# MCU.net
KiCad netlist of a schematic drawn in Altium Designer
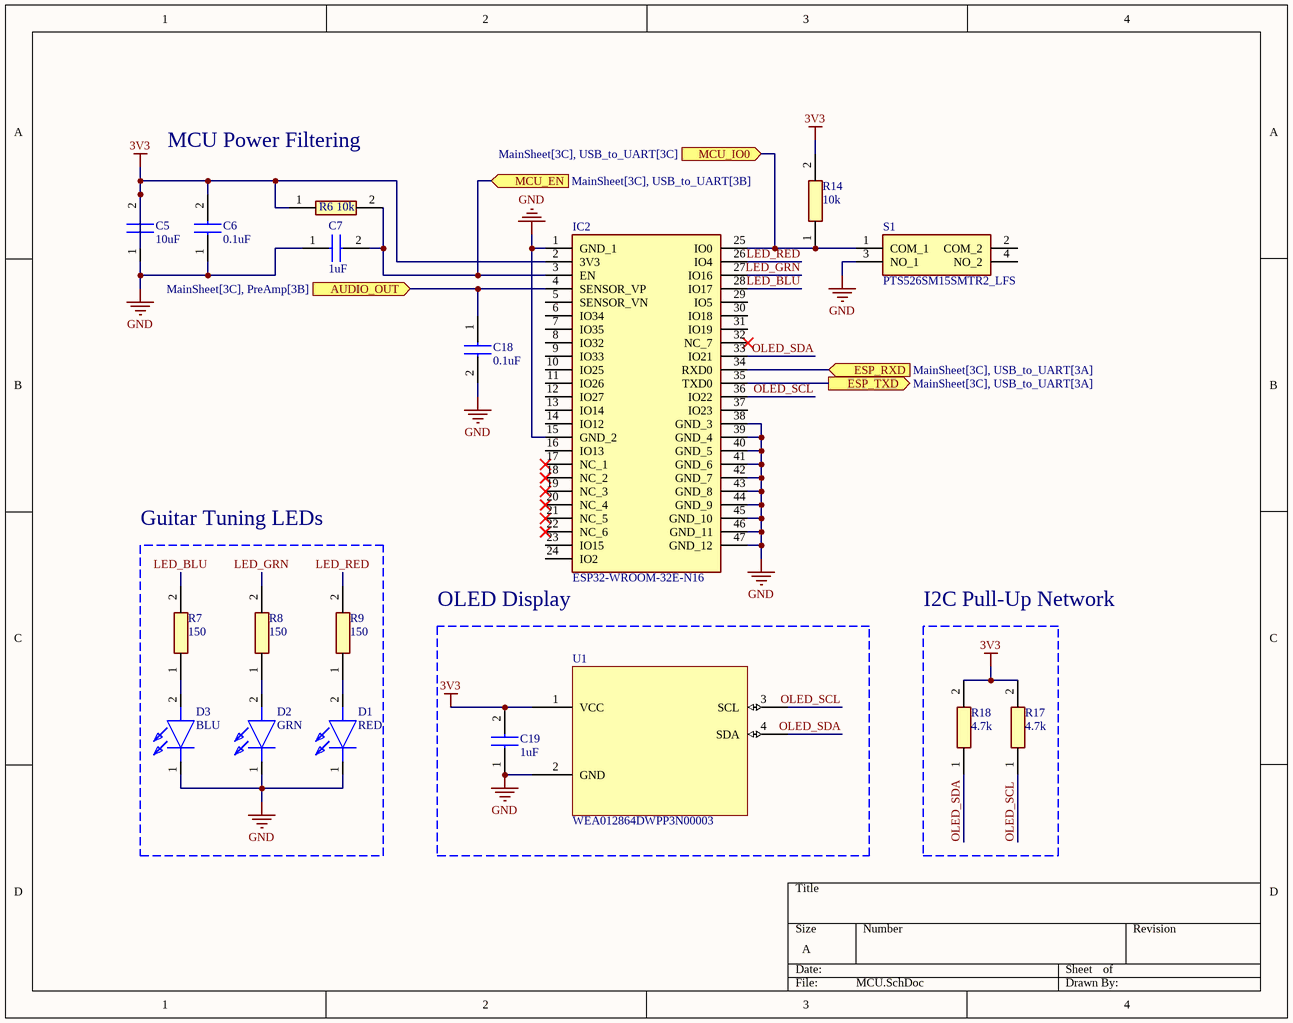
[diagram p0: MCU.SchDoc]

(export (version "E")
  (design (tool "Eeschema 10.0.6"))
  (components
    (comp (ref "C5")
      (value "10uF")
      (footprint "SamacSys:CAPC2012X140N")
      (description "Capacitor")
      (fields (field (name "MANUFACTURER_PART_NUMBER") "C0805C106K8PACTU-2.5"))
      (libsource (lib "Schlib1") (part "10uF Capacitor 0805"))
    )
    (comp (ref "C6")
      (value "0.1uF")
      (footprint "SamacSys:CAPC2012X88N")
      (description "Capacitor")
      (fields (field (name "MANUFACTURER_PART_NUMBER") "C0805C104K5RAC-TU"))
      (libsource (lib "Schlib1") (part "0.1uF Capacitor 0805"))
    )
    (comp (ref "C7")
      (value "1uF")
      (footprint "SamacSys:CAPC2012X145N")
      (description "Capacitor")
      (fields
        (field (name "MANUFACTURER_PART_NUMBER") "GRM21BR71A105KA01L")
        (field (name "MOUSER PART NUMBER") "81-GRM40X105K10L")
      )
      (libsource (lib "Schlib1") (part "1uF Capacitor 0805"))
    )
    (comp (ref "C18")
      (value "0.1uF")
      (footprint "SamacSys:CAPC2012X88N")
      (description "Capacitor")
      (fields (field (name "MANUFACTURER_PART_NUMBER") "C0805C104K5RAC-TU"))
      (libsource (lib "Schlib1") (part "0.1uF Capacitor 0805"))
    )
    (comp (ref "C19")
      (value "1uF")
      (footprint "SamacSys:GRM21BR60J226ME39L")
      (description "Capacitor")
      (fields
        (field (name "MANUFACTURER_PART_NUMBER") "GRM21BR61A105KA01L")
        (field (name "MOUSER PART NUMBER") "81-GRM21R61A105KA01L")
      )
      (libsource (lib "Schlib1") (part "1uF Capacitor"))
    )
    (comp (ref "D1")
      (value "RED")
      (footprint "SamacSys:LEDC2012X85N")
      (description "LED")
      (fields
        (field (name "MANUFACTURER_PART_NUMBER") "APT2012EC")
        (field (name "MOUSER PART NUMBER") "604-APT2012EC")
      )
      (libsource (lib "Schlib1") (part "Red LED"))
    )
    (comp (ref "D2")
      (value "GRN")
      (footprint "SamacSys:LEDC2012X85N")
      (description "LED")
      (fields
        (field (name "MANUFACTURER_PART_NUMBER") "APT2012SGC")
        (field (name "MOUSER PART NUMBER") "604-APT2012SGC")
      )
      (libsource (lib "Schlib1") (part "Green LED"))
    )
    (comp (ref "D3")
      (value "BLU")
      (footprint "SamacSys:LEDC2012X85N")
      (description "LED")
      (fields
        (field (name "MANUFACTURER_PART_NUMBER") "APT2012LVBC/D")
        (field (name "MOUSER PART NUMBER") "604-APT2012LVBCD")
      )
      (libsource (lib "Schlib1") (part "Blue LED"))
    )
    (comp (ref "IC2")
      (value "ESP32-WROOM-32E-N16")
      (footprint "SamacSys:ESP32WROOM32EN16")
      (description "Integrated Circuit")
      (fields (field (name "MOUSER PART NUMBER") "356-ESP32WRM32E128PH"))
      (libsource (lib "*") (part "ESP32-WROOM-32E-N16"))
    )
    (comp (ref "R6")
      (value "10k")
      (footprint "SamacSys:ERA6AEB101V")
      (description "Resistor")
      (fields
        (field (name "MANUFACTURER_PART_NUMBER") "ERA-6AED103V")
        (field (name "MOUSER PART NUMBER") "667-ERA-6AED103V")
      )
      (libsource (lib "Schlib1") (part "10k Resistor 0805"))
    )
    (comp (ref "R7")
      (value "150")
      (footprint "SamacSys:RESC2012X50N")
      (description "Resistor")
      (fields
        (field (name "MANUFACTURER_PART_NUMBER") "CRCW0805150RFKEA")
        (field (name "MOUSER PART NUMBER") "71-CRCW0805-150-E3")
      )
      (libsource (lib "Schlib1") (part "150 Resistor 0805"))
    )
    (comp (ref "R8")
      (value "150")
      (footprint "SamacSys:RESC2012X50N")
      (description "Resistor")
      (fields
        (field (name "MANUFACTURER_PART_NUMBER") "CRCW0805150RFKEA")
        (field (name "MOUSER PART NUMBER") "71-CRCW0805-150-E3")
      )
      (libsource (lib "Schlib1") (part "150 Resistor 0805"))
    )
    (comp (ref "R9")
      (value "150")
      (footprint "SamacSys:RESC2012X50N")
      (description "Resistor")
      (fields
        (field (name "MANUFACTURER_PART_NUMBER") "CRCW0805150RFKEA")
        (field (name "MOUSER PART NUMBER") "71-CRCW0805-150-E3")
      )
      (libsource (lib "Schlib1") (part "150 Resistor 0805"))
    )
    (comp (ref "R14")
      (value "10k")
      (footprint "SamacSys:ERA6AEB101V")
      (description "Resistor")
      (fields
        (field (name "MANUFACTURER_PART_NUMBER") "ERA-6AED103V")
        (field (name "MOUSER PART NUMBER") "667-ERA-6AED103V")
      )
      (libsource (lib "") (part "10k Resistor 0805_1"))
    )
    (comp (ref "R17")
      (value "4.7k")
      (footprint "SamacSys:RESC2012X60N")
      (description "Resistor")
      (fields
        (field (name "MANUFACTURER_PART_NUMBER") "RC0805FR-074K7L")
        (field (name "MOUSER PART NUMBER") "603-RC0805FR-074K7L")
      )
      (libsource (lib "Schlib1") (part "4.7k Resistor 0805"))
    )
    (comp (ref "R18")
      (value "4.7k")
      (footprint "SamacSys:RESC2012X60N")
      (description "Resistor")
      (fields
        (field (name "MANUFACTURER_PART_NUMBER") "RC0805FR-074K7L")
        (field (name "MOUSER PART NUMBER") "603-RC0805FR-074K7L")
      )
      (libsource (lib "Schlib1") (part "4.7k Resistor 0805"))
    )
    (comp (ref "S1")
      (value "PTS526SM15SMTR2_LFS")
      (footprint "SamacSys:PTS526SM15SMTR2LFS")
      (description "Switch")
      (fields
        (field (name "MANUFACTURER_PART_NUMBER") "PTS526SM15SMTR2 LFS")
        (field (name "MOUSER PART NUMBER") "611-PTS526SM15SMTR2L")
      )
      (libsource (lib "*") (part "PTS526SM15SMTR2_LFS"))
    )
    (comp (ref "U1")
      (value "WEA012864DWPP3N00003")
      (footprint "PcbLib1:OLED_128x64_I2C")
      (description "OLED_128x64_I2C")
      (libsource (lib "Schlib1") (part "WEA012864DWPP3N00003"))
    )
  )
  (nets
    (net (code "1") (name "/AUDIO_OUT") (class "Default")
      (node (ref "C18") (pin "1") (pinfunction "1_1") (pintype "passive"))
      (node (ref "IC2") (pin "4") (pinfunction "SENSOR_VP_4") (pintype "passive"))
    )
    (net (code "2") (name "/ESP_RXD") (class "Default")
      (node (ref "IC2") (pin "34") (pinfunction "RXD0_34") (pintype "passive"))
    )
    (net (code "3") (name "/ESP_TXD") (class "Default")
      (node (ref "IC2") (pin "35") (pinfunction "TXD0_35") (pintype "passive"))
    )
    (net (code "4") (name "/LED_BLU") (class "Default")
      (node (ref "IC2") (pin "28") (pinfunction "IO17_28") (pintype "passive"))
      (node (ref "R7") (pin "2") (pinfunction "2_2") (pintype "passive"))
    )
    (net (code "5") (name "/LED_GRN") (class "Default")
      (node (ref "IC2") (pin "27") (pinfunction "IO16_27") (pintype "passive"))
      (node (ref "R8") (pin "2") (pinfunction "2_2") (pintype "passive"))
    )
    (net (code "6") (name "/LED_RED") (class "Default")
      (node (ref "IC2") (pin "26") (pinfunction "IO4_26") (pintype "passive"))
      (node (ref "R9") (pin "2") (pinfunction "2_2") (pintype "passive"))
    )
    (net (code "7") (name "/MCU_EN") (class "Default")
      (node (ref "C7") (pin "2") (pinfunction "2_2") (pintype "passive"))
      (node (ref "IC2") (pin "3") (pinfunction "EN_3") (pintype "passive"))
      (node (ref "R6") (pin "2") (pinfunction "2_2") (pintype "passive"))
    )
    (net (code "8") (name "/MCU_IO0") (class "Default")
      (node (ref "IC2") (pin "25") (pinfunction "IO0_25") (pintype "passive"))
      (node (ref "R14") (pin "1") (pinfunction "1_1") (pintype "passive"))
      (node (ref "S1") (pin "1") (pinfunction "COM_1_1") (pintype "passive"))
    )
    (net (code "9") (name "/OLED_SCL") (class "Default")
      (node (ref "IC2") (pin "36") (pinfunction "IO22_36") (pintype "passive"))
      (node (ref "R17") (pin "1") (pinfunction "1_1") (pintype "passive"))
      (node (ref "U1") (pin "3") (pinfunction "SCL_3") (pintype "bidirectional"))
    )
    (net (code "10") (name "/OLED_SDA") (class "Default")
      (node (ref "IC2") (pin "33") (pinfunction "IO21_33") (pintype "passive"))
      (node (ref "R18") (pin "1") (pinfunction "1_1") (pintype "passive"))
      (node (ref "U1") (pin "4") (pinfunction "SDA_4") (pintype "bidirectional"))
    )
    (net (code "11") (name "3V3") (class "Default")
      (node (ref "C19") (pin "2") (pinfunction "2_2") (pintype "passive"))
      (node (ref "C5") (pin "2") (pinfunction "2_2") (pintype "passive"))
      (node (ref "C6") (pin "2") (pinfunction "2_2") (pintype "passive"))
      (node (ref "IC2") (pin "2") (pinfunction "3V3_2") (pintype "passive"))
      (node (ref "R14") (pin "2") (pinfunction "2_2") (pintype "passive"))
      (node (ref "R17") (pin "2") (pinfunction "2_2") (pintype "passive"))
      (node (ref "R18") (pin "2") (pinfunction "2_2") (pintype "passive"))
      (node (ref "R6") (pin "1") (pinfunction "1_1") (pintype "passive"))
      (node (ref "U1") (pin "1") (pinfunction "VCC_1") (pintype "power_in"))
    )
    (net (code "12") (name "GND") (class "Default")
      (node (ref "C18") (pin "2") (pinfunction "2_2") (pintype "passive"))
      (node (ref "C19") (pin "1") (pinfunction "1_1") (pintype "passive"))
      (node (ref "C5") (pin "1") (pinfunction "1_1") (pintype "passive"))
      (node (ref "C6") (pin "1") (pinfunction "1_1") (pintype "passive"))
      (node (ref "C7") (pin "1") (pinfunction "1_1") (pintype "passive"))
      (node (ref "D1") (pin "1") (pinfunction "K_1") (pintype "passive"))
      (node (ref "D2") (pin "1") (pinfunction "K_1") (pintype "passive"))
      (node (ref "D3") (pin "1") (pinfunction "K_1") (pintype "passive"))
      (node (ref "IC2") (pin "1") (pinfunction "GND_1_1") (pintype "passive"))
      (node (ref "IC2") (pin "15") (pinfunction "GND_2_15") (pintype "passive"))
      (node (ref "IC2") (pin "38") (pinfunction "GND_3_38") (pintype "passive"))
      (node (ref "IC2") (pin "39") (pinfunction "GND_4_39") (pintype "passive"))
      (node (ref "IC2") (pin "40") (pinfunction "GND_5_40") (pintype "passive"))
      (node (ref "IC2") (pin "41") (pinfunction "GND_6_41") (pintype "passive"))
      (node (ref "IC2") (pin "42") (pinfunction "GND_7_42") (pintype "passive"))
      (node (ref "IC2") (pin "43") (pinfunction "GND_8_43") (pintype "passive"))
      (node (ref "IC2") (pin "44") (pinfunction "GND_9_44") (pintype "passive"))
      (node (ref "IC2") (pin "45") (pinfunction "GND_10_45") (pintype "passive"))
      (node (ref "IC2") (pin "46") (pinfunction "GND_11_46") (pintype "passive"))
      (node (ref "IC2") (pin "47") (pinfunction "GND_12_47") (pintype "passive"))
      (node (ref "S1") (pin "3") (pinfunction "NO_1_3") (pintype "passive"))
      (node (ref "U1") (pin "2") (pinfunction "GND_2") (pintype "power_in"))
    )
    (net (code "13") (name "Net-(D1-A)") (class "Default")
      (node (ref "D1") (pin "2") (pinfunction "A_2") (pintype "passive"))
      (node (ref "R9") (pin "1") (pinfunction "1_1") (pintype "passive"))
    )
    (net (code "14") (name "Net-(D2-A)") (class "Default")
      (node (ref "D2") (pin "2") (pinfunction "A_2") (pintype "passive"))
      (node (ref "R8") (pin "1") (pinfunction "1_1") (pintype "passive"))
    )
    (net (code "15") (name "Net-(D3-A)") (class "Default")
      (node (ref "D3") (pin "2") (pinfunction "A_2") (pintype "passive"))
      (node (ref "R7") (pin "1") (pinfunction "1_1") (pintype "passive"))
    )
    (net (code "16") (name "unconnected-(IC2-IO2-Pad24)") (class "Default")
      (node (ref "IC2") (pin "24") (pinfunction "IO2_24") (pintype "passive"))
    )
    (net (code "17") (name "unconnected-(IC2-IO5-Pad29)") (class "Default")
      (node (ref "IC2") (pin "29") (pinfunction "IO5_29") (pintype "passive"))
    )
    (net (code "18") (name "unconnected-(IC2-IO12-Pad14)") (class "Default")
      (node (ref "IC2") (pin "14") (pinfunction "IO12_14") (pintype "passive"))
    )
    (net (code "19") (name "unconnected-(IC2-IO13-Pad16)") (class "Default")
      (node (ref "IC2") (pin "16") (pinfunction "IO13_16") (pintype "passive"))
    )
    (net (code "20") (name "unconnected-(IC2-IO14-Pad13)") (class "Default")
      (node (ref "IC2") (pin "13") (pinfunction "IO14_13") (pintype "passive"))
    )
    (net (code "21") (name "unconnected-(IC2-IO15-Pad23)") (class "Default")
      (node (ref "IC2") (pin "23") (pinfunction "IO15_23") (pintype "passive"))
    )
    (net (code "22") (name "unconnected-(IC2-IO18-Pad30)") (class "Default")
      (node (ref "IC2") (pin "30") (pinfunction "IO18_30") (pintype "passive"))
    )
    (net (code "23") (name "unconnected-(IC2-IO19-Pad31)") (class "Default")
      (node (ref "IC2") (pin "31") (pinfunction "IO19_31") (pintype "passive"))
    )
    (net (code "24") (name "unconnected-(IC2-IO23-Pad37)") (class "Default")
      (node (ref "IC2") (pin "37") (pinfunction "IO23_37") (pintype "passive"))
    )
    (net (code "25") (name "unconnected-(IC2-IO25-Pad10)") (class "Default")
      (node (ref "IC2") (pin "10") (pinfunction "IO25_10") (pintype "passive"))
    )
    (net (code "26") (name "unconnected-(IC2-IO26-Pad11)") (class "Default")
      (node (ref "IC2") (pin "11") (pinfunction "IO26_11") (pintype "passive"))
    )
    (net (code "27") (name "unconnected-(IC2-IO27-Pad12)") (class "Default")
      (node (ref "IC2") (pin "12") (pinfunction "IO27_12") (pintype "passive"))
    )
    (net (code "28") (name "unconnected-(IC2-IO32-Pad8)") (class "Default")
      (node (ref "IC2") (pin "8") (pinfunction "IO32_8") (pintype "passive"))
    )
    (net (code "29") (name "unconnected-(IC2-IO33-Pad9)") (class "Default")
      (node (ref "IC2") (pin "9") (pinfunction "IO33_9") (pintype "passive"))
    )
    (net (code "30") (name "unconnected-(IC2-IO34-Pad6)") (class "Default")
      (node (ref "IC2") (pin "6") (pinfunction "IO34_6") (pintype "passive"))
    )
    (net (code "31") (name "unconnected-(IC2-IO35-Pad7)") (class "Default")
      (node (ref "IC2") (pin "7") (pinfunction "IO35_7") (pintype "passive"))
    )
    (net (code "32") (name "unconnected-(IC2-NC_1-Pad17)") (class "Default")
      (node (ref "IC2") (pin "17") (pinfunction "NC_1_17") (pintype "passive+no_connect"))
    )
    (net (code "33") (name "unconnected-(IC2-NC_2-Pad18)") (class "Default")
      (node (ref "IC2") (pin "18") (pinfunction "NC_2_18") (pintype "passive+no_connect"))
    )
    (net (code "34") (name "unconnected-(IC2-NC_3-Pad19)") (class "Default")
      (node (ref "IC2") (pin "19") (pinfunction "NC_3_19") (pintype "passive+no_connect"))
    )
    (net (code "35") (name "unconnected-(IC2-NC_4-Pad20)") (class "Default")
      (node (ref "IC2") (pin "20") (pinfunction "NC_4_20") (pintype "passive+no_connect"))
    )
    (net (code "36") (name "unconnected-(IC2-NC_5-Pad21)") (class "Default")
      (node (ref "IC2") (pin "21") (pinfunction "NC_5_21") (pintype "passive+no_connect"))
    )
    (net (code "37") (name "unconnected-(IC2-NC_6-Pad22)") (class "Default")
      (node (ref "IC2") (pin "22") (pinfunction "NC_6_22") (pintype "passive+no_connect"))
    )
    (net (code "38") (name "unconnected-(IC2-NC_7-Pad32)") (class "Default")
      (node (ref "IC2") (pin "32") (pinfunction "NC_7_32") (pintype "passive+no_connect"))
    )
    (net (code "39") (name "unconnected-(IC2-SENSOR_VN-Pad5)") (class "Default")
      (node (ref "IC2") (pin "5") (pinfunction "SENSOR_VN_5") (pintype "passive"))
    )
    (net (code "40") (name "unconnected-(S1-COM_2-Pad2)") (class "Default")
      (node (ref "S1") (pin "2") (pinfunction "COM_2_2") (pintype "passive"))
    )
    (net (code "41") (name "unconnected-(S1-NO_2-Pad4)") (class "Default")
      (node (ref "S1") (pin "4") (pinfunction "NO_2_4") (pintype "passive"))
    )
  )
)
